# PP_0_3.net
KiCad netlist of a schematic drawn in Altium Designer
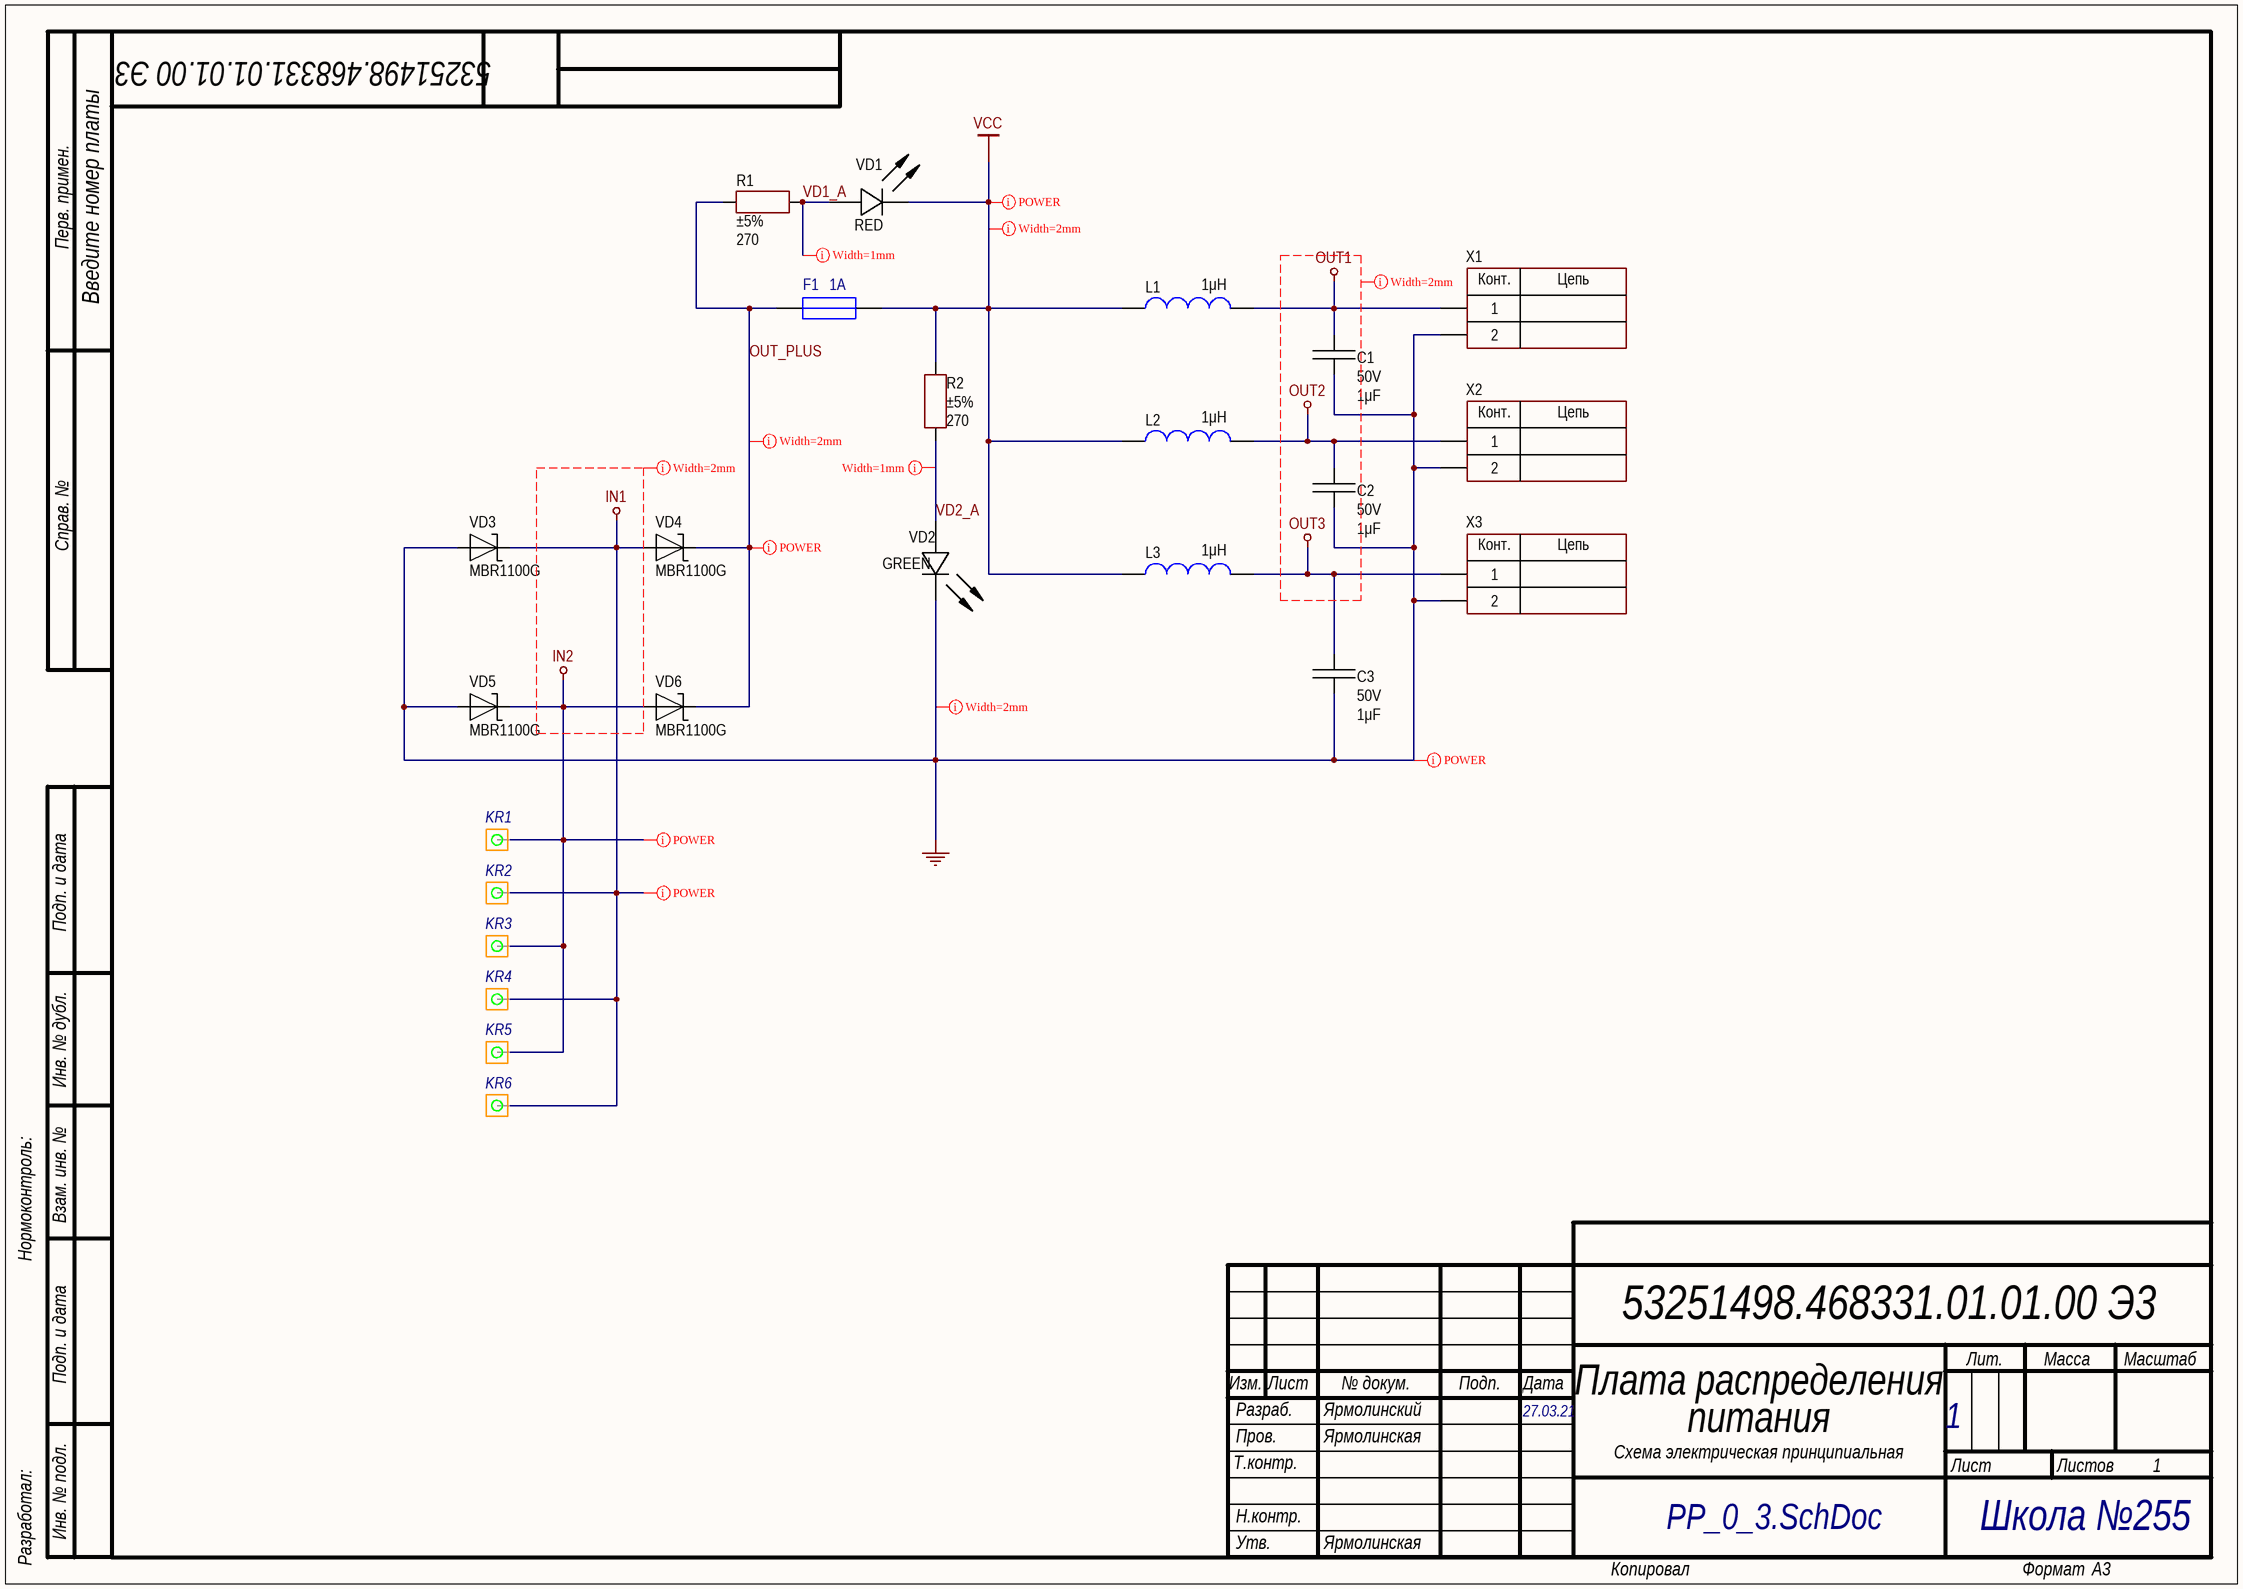
[diagram p0: PP_0_3.SchDoc]

(export (version "E")
  (design (tool "Eeschema 10.0.6"))
  (components
    (comp (ref "C1")
      (value "1μF")
      (footprint "CAP: 0805, Thru-Hole")
      (description "К10-17 0805")
      (fields
        (field (name "MANUFACTURER") "Murata")
        (field (name "PARTNUMBER") "RDER71H105K2K1C03B")
        (field (name "VOLTAGE") "50V")
      )
      (libsource (lib "RAZNOE") (part "Ceramic_0805"))
    )
    (comp (ref "C2")
      (value "1μF")
      (footprint "CAP: 0805, Thru-Hole")
      (description "К10-17 0805")
      (fields
        (field (name "MANUFACTURER") "Murata")
        (field (name "PARTNUMBER") "RDER71H105K2K1C03B")
        (field (name "VOLTAGE") "50V")
      )
      (libsource (lib "RAZNOE") (part "Ceramic_0805"))
    )
    (comp (ref "C3")
      (value "1μF")
      (footprint "CAP: 0805, Thru-Hole")
      (description "К10-17 0805")
      (fields
        (field (name "MANUFACTURER") "Murata")
        (field (name "PARTNUMBER") "RDER71H105K2K1C03B")
        (field (name "VOLTAGE") "50V")
      )
      (libsource (lib "RAZNOE") (part "Ceramic_0805"))
    )
    (comp (ref "F1")
      (value "1A")
      (footprint "MF-R_Style_1")
      (description "Fuse 1A")
      (fields (field (name "PARTNUMBER") "MF-R300") (field (name "PUBLISHER") "Altium Limited"))
      (libsource (lib "RAZNOE") (part "Fuse 1A"))
    )
    (comp (ref "KR1")
      (value "KR_3")
      (footprint "KR_3_0")
      (description "Mounting point")
      (libsource (lib "Check_Points") (part "KR_3"))
    )
    (comp (ref "KR2")
      (value "KR_3")
      (footprint "KR_3_0")
      (description "Mounting point")
      (libsource (lib "Check_Points") (part "KR_3"))
    )
    (comp (ref "KR3")
      (value "KR_3")
      (footprint "KR_3_0")
      (description "Mounting point")
      (libsource (lib "Check_Points") (part "KR_3"))
    )
    (comp (ref "KR4")
      (value "KR_3")
      (footprint "KR_3_0")
      (description "Mounting point")
      (libsource (lib "Check_Points") (part "KR_3"))
    )
    (comp (ref "KR5")
      (value "KR_3")
      (footprint "KR_3_0")
      (description "Mounting point")
      (libsource (lib "Check_Points") (part "KR_3"))
    )
    (comp (ref "KR6")
      (value "KR_3")
      (footprint "KR_3_0")
      (description "Mounting point")
      (libsource (lib "Check_Points") (part "KR_3"))
    )
    (comp (ref "L1")
      (value "1μH")
      (footprint "IND: BL-01")
      (description "Индуктивность  подавления ЭМП")
      (fields (field (name "MANUFACTURER") "Murata") (field (name "PARTNUMBER") "BL01RN1A2A2B"))
      (libsource (lib "RAZNOE") (part "IND{colon} BL-01"))
    )
    (comp (ref "L2")
      (value "1μH")
      (footprint "IND: BL-01")
      (description "Индуктивность  подавления ЭМП")
      (fields (field (name "MANUFACTURER") "Murata") (field (name "PARTNUMBER") "30201567"))
      (libsource (lib "RAZNOE") (part "IND{colon} BL-01"))
    )
    (comp (ref "L3")
      (value "1μH")
      (footprint "IND: BL-01")
      (description "Индуктивность  подавления ЭМП")
      (fields (field (name "MANUFACTURER") "Murata") (field (name "PARTNUMBER") "30201567"))
      (libsource (lib "RAZNOE") (part "IND{colon} BL-01"))
    )
    (comp (ref "R1")
      (value "270")
      (footprint "AXIAL-0.3")
      (fields
        (field (name "MANUFACTURER") "Yageo")
        (field (name "PARTNUMBER") "СF-1/4W-100RF")
        (field (name "VALUEMANUFACTURERPARTNUMBER") "Resistor film, 270, ±5%, CF-25, 0.25W, -55...+125°C")
        (field (name "TOLERANCE") "±5%")
      )
      (libsource (lib "") (part "ResistorCF-25_1"))
    )
    (comp (ref "R2")
      (value "270")
      (footprint "AXIAL-0.3")
      (fields
        (field (name "MANUFACTURER") "Yageo")
        (field (name "PARTNUMBER") "СF-1/4W-100RF")
        (field (name "VALUEMANUFACTURERPARTNUMBER") "Resistor film, 270, ±5%, CF-25, 0.25W, -55...+125°C")
        (field (name "TOLERANCE") "±5%")
      )
      (libsource (lib "REZISTOR_THRU") (part "ResistorCF-25"))
    )
    (comp (ref "VD1")
      (value "~")
      (footprint "LED: 3MM_R")
      (fields
        (field (name "VALUEMANUFACTURERPARTNUMBER") "LED, Red, *, *, 5mm, -55...+150°C")
        (field (name "PARTNUMBER") "GNL-5013HT")
        (field (name "COLOR") "RED")
      )
      (libsource (lib "diode") (part "LED_single"))
    )
    (comp (ref "VD2")
      (value "~")
      (footprint "LED: 3MM_G")
      (fields
        (field (name "VALUEMANUFACTURERPARTNUMBER") "LED, Green, *, *, 5mm, -55...+150°C")
        (field (name "PARTNUMBER") "GNL-5013GT")
        (field (name "COLOR") "GREEN")
      )
      (libsource (lib "diode") (part "LED_single"))
    )
    (comp (ref "VD3")
      (value "~")
      (footprint "DIODE: DO-41")
      (fields
        (field (name "MANUFACTURER") "Diodes Incorporated")
        (field (name "VALUEMANUFACTURERPARTNUMBER") "Schottky diode, 100V, 1A, 1V, 15pF, DO-41, -55...+150°C")
        (field (name "VOLTAGE") "100V")
        (field (name "PARTNUMBER") "MBR1100G")
      )
      (libsource (lib "DIODE_SHOTTKI") (part "Schottky_1A"))
    )
    (comp (ref "VD4")
      (value "~")
      (footprint "DIODE: DO-41")
      (fields
        (field (name "MANUFACTURER") "Diodes Incorporated")
        (field (name "VALUEMANUFACTURERPARTNUMBER") "Schottky diode, 100V, 1A, 1V, 15pF, DO-41, -55...+150°C")
        (field (name "VOLTAGE") "100V")
        (field (name "PARTNUMBER") "MBR1100G")
      )
      (libsource (lib "DIODE_SHOTTKI") (part "Schottky_1A"))
    )
    (comp (ref "VD5")
      (value "~")
      (footprint "DIODE: DO-41")
      (fields
        (field (name "MANUFACTURER") "Diodes Incorporated")
        (field (name "VALUEMANUFACTURERPARTNUMBER") "Schottky diode, 100V, 1A, 1V, 15pF, DO-41, -55...+150°C")
        (field (name "VOLTAGE") "100V")
        (field (name "PARTNUMBER") "MBR1100G")
      )
      (libsource (lib "DIODE_SHOTTKI") (part "Schottky_1A"))
    )
    (comp (ref "VD6")
      (value "~")
      (footprint "DIODE: DO-41")
      (fields
        (field (name "MANUFACTURER") "Diodes Incorporated")
        (field (name "VALUEMANUFACTURERPARTNUMBER") "Schottky diode, 100V, 1A, 1V, 15pF, DO-41, -55...+150°C")
        (field (name "VOLTAGE") "100V")
        (field (name "PARTNUMBER") "MBR1100G")
      )
      (libsource (lib "DIODE_SHOTTKI") (part "Schottky_1A"))
    )
    (comp (ref "X1")
      (value "~")
      (footprint "CON: DG350-3.5-02P")
      (fields
        (field (name "MANUFACTURER") "Degson")
        (field (name "VALUEMANUFACTURERPARTNUMBER") "Terminal connector, 2pin, 3.5mm, 300VAC, 10A")
        (field (name "PARTNUMBER") "DG350-3.5-02P-14")
      )
      (libsource (lib "connector") (part "Connector_terminal_2pin"))
    )
    (comp (ref "X2")
      (value "~")
      (footprint "CON: DG350-3.5-02P")
      (fields
        (field (name "MANUFACTURER") "Degson")
        (field (name "VALUEMANUFACTURERPARTNUMBER") "Terminal connector, 2pin, 3.5mm, 300VAC, 10A")
        (field (name "PARTNUMBER") "DG350-3.5-02P-14")
      )
      (libsource (lib "connector") (part "Connector_terminal_2pin"))
    )
    (comp (ref "X3")
      (value "~")
      (footprint "CON: DG350-3.5-02P")
      (fields
        (field (name "MANUFACTURER") "Degson")
        (field (name "VALUEMANUFACTURERPARTNUMBER") "Terminal connector, 2pin, 3.5mm, 300VAC, 10A")
        (field (name "PARTNUMBER") "DG350-3.5-02P-14")
      )
      (libsource (lib "connector") (part "Connector_terminal_2pin"))
    )
  )
  (nets
    (net (code "1") (name "/OUT_PLUS") (class "Default")
      (node (ref "F1") (pin "1") (pinfunction "1_1") (pintype "passive"))
      (node (ref "R1") (pin "1") (pinfunction "1_1") (pintype "passive"))
      (node (ref "VD4") (pin "2") (pinfunction "2_2") (pintype "passive"))
      (node (ref "VD6") (pin "2") (pinfunction "2_2") (pintype "passive"))
    )
    (net (code "2") (name "/VD1_A") (class "Default")
      (node (ref "R1") (pin "2") (pinfunction "2_2") (pintype "passive"))
      (node (ref "VD1") (pin "1") (pinfunction "A_1") (pintype "passive"))
    )
    (net (code "3") (name "/VD2_A") (class "Default")
      (node (ref "R2") (pin "1") (pinfunction "1_1") (pintype "passive"))
      (node (ref "VD2") (pin "1") (pinfunction "A_1") (pintype "passive"))
    )
    (net (code "4") (name "GND") (class "Default")
      (node (ref "C1") (pin "2") (pinfunction "2_2") (pintype "passive"))
      (node (ref "C2") (pin "1") (pinfunction "1_1") (pintype "passive"))
      (node (ref "C3") (pin "2") (pinfunction "2_2") (pintype "passive"))
      (node (ref "VD2") (pin "2") (pinfunction "C_2") (pintype "passive"))
      (node (ref "VD3") (pin "1") (pinfunction "1_1") (pintype "passive"))
      (node (ref "VD5") (pin "1") (pinfunction "1_1") (pintype "passive"))
      (node (ref "X1") (pin "2") (pinfunction "2_2") (pintype "passive"))
      (node (ref "X2") (pin "2") (pinfunction "2_2") (pintype "passive"))
      (node (ref "X3") (pin "2") (pinfunction "2_2") (pintype "passive"))
    )
    (net (code "5") (name "IN1") (class "Default")
      (node (ref "KR2") (pin "0") (pinfunction "0_0") (pintype "passive"))
      (node (ref "KR4") (pin "0") (pinfunction "0_0") (pintype "passive"))
      (node (ref "KR6") (pin "0") (pinfunction "0_0") (pintype "passive"))
      (node (ref "VD3") (pin "2") (pinfunction "2_2") (pintype "passive"))
      (node (ref "VD4") (pin "1") (pinfunction "1_1") (pintype "passive"))
    )
    (net (code "6") (name "IN2") (class "Default")
      (node (ref "KR1") (pin "0") (pinfunction "0_0") (pintype "passive"))
      (node (ref "KR3") (pin "0") (pinfunction "0_0") (pintype "passive"))
      (node (ref "KR5") (pin "0") (pinfunction "0_0") (pintype "passive"))
      (node (ref "VD5") (pin "2") (pinfunction "2_2") (pintype "passive"))
      (node (ref "VD6") (pin "1") (pinfunction "1_1") (pintype "passive"))
    )
    (net (code "7") (name "OUT1") (class "Default")
      (node (ref "C1") (pin "1") (pinfunction "1_1") (pintype "passive"))
      (node (ref "L1") (pin "1") (pinfunction "1_1") (pintype "passive"))
      (node (ref "X1") (pin "1") (pinfunction "1_1") (pintype "passive"))
    )
    (net (code "8") (name "OUT2") (class "Default")
      (node (ref "C2") (pin "2") (pinfunction "2_2") (pintype "passive"))
      (node (ref "L2") (pin "1") (pinfunction "1_1") (pintype "passive"))
      (node (ref "X2") (pin "1") (pinfunction "1_1") (pintype "passive"))
    )
    (net (code "9") (name "OUT3") (class "Default")
      (node (ref "C3") (pin "1") (pinfunction "1_1") (pintype "passive"))
      (node (ref "L3") (pin "1") (pinfunction "1_1") (pintype "passive"))
      (node (ref "X3") (pin "1") (pinfunction "1_1") (pintype "passive"))
    )
    (net (code "10") (name "VCC") (class "Default")
      (node (ref "F1") (pin "2") (pinfunction "2_2") (pintype "passive"))
      (node (ref "L1") (pin "2") (pinfunction "2_2") (pintype "passive"))
      (node (ref "L2") (pin "2") (pinfunction "2_2") (pintype "passive"))
      (node (ref "L3") (pin "2") (pinfunction "2_2") (pintype "passive"))
      (node (ref "R2") (pin "2") (pinfunction "2_2") (pintype "passive"))
      (node (ref "VD1") (pin "2") (pinfunction "C_2") (pintype "passive"))
    )
  )
)
